# c64-uni-cart.net
KiCad netlist of a schematic drawn in EAGLE
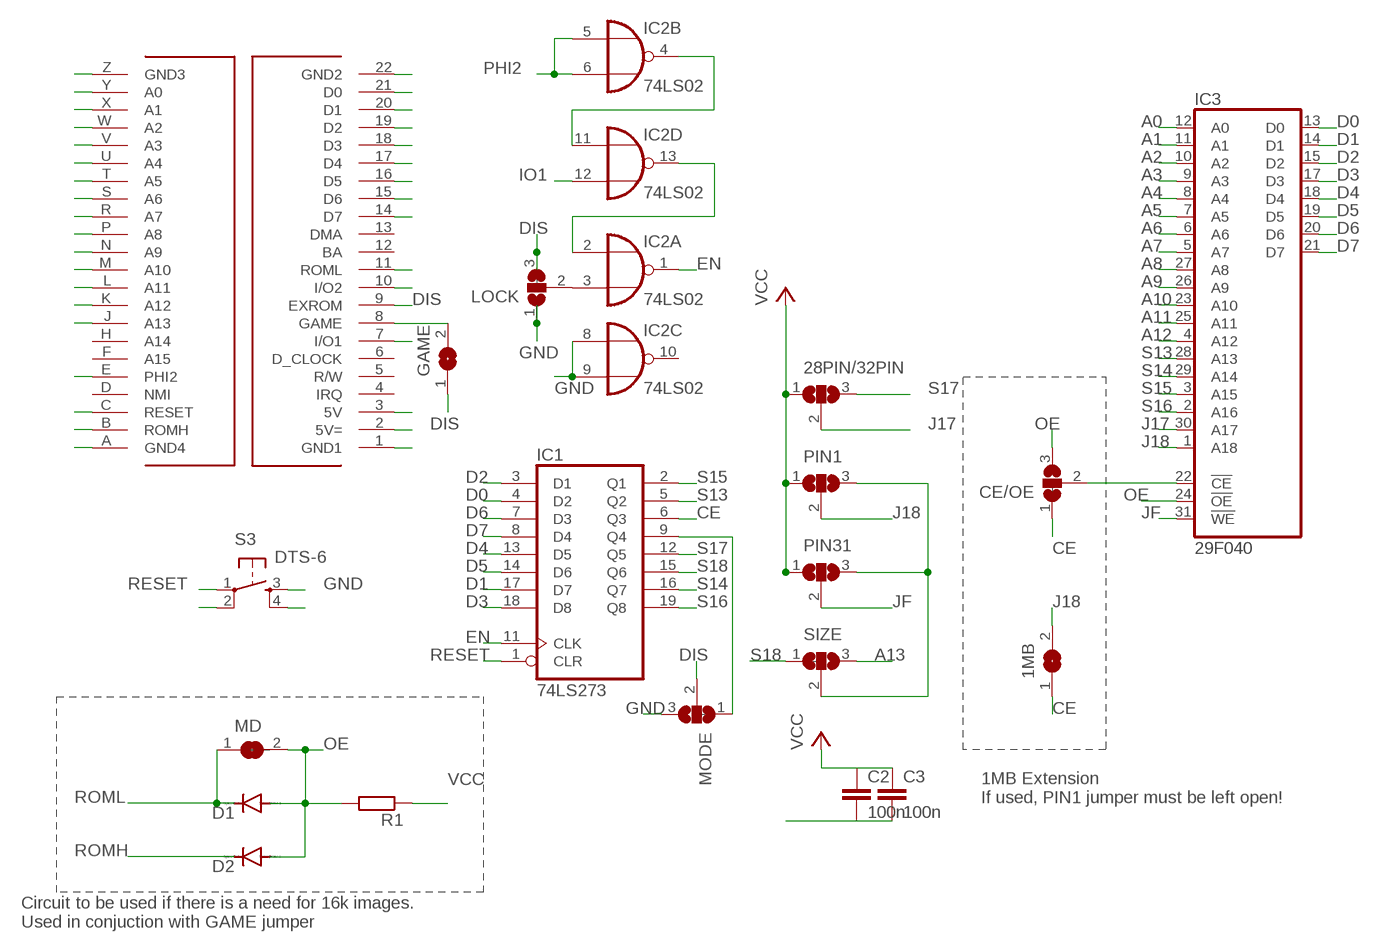
[diagram p0: schematic, sheet 1]

(export (version "E")
  (design (tool "Eeschema 10.0.6"))
  (components
    (comp (ref "1MB") (value "SJ") (footprint "eagle-import:SJ") (libsource (lib "eagle-import") (part "SJ")))
    (comp (ref "28PIN/32PIN")
      (value "SJ2W")
      (footprint "eagle-import:SJ_2")
      (libsource (lib "eagle-import") (part "SJ2W"))
    )
    (comp (ref "C2")
      (value "100n")
      (footprint "eagle-import:C025-024X044")
      (libsource (lib "eagle-import") (part "C-EU025-024X044"))
    )
    (comp (ref "C3")
      (value "100n")
      (footprint "eagle-import:C025-024X044")
      (libsource (lib "eagle-import") (part "C-EU025-024X044"))
    )
    (comp (ref "CE/OE")
      (value "SJ2W")
      (footprint "eagle-import:SJ_2")
      (libsource (lib "eagle-import") (part "SJ2W"))
    )
    (comp (ref "D1")
      (value "DIODE-MINIMELF")
      (footprint "eagle-import:MINIMELF")
      (libsource (lib "eagle-import") (part "DIODE-MINIMELF"))
    )
    (comp (ref "D2")
      (value "DIODE-MINIMELF")
      (footprint "eagle-import:MINIMELF")
      (libsource (lib "eagle-import") (part "DIODE-MINIMELF"))
    )
    (comp (ref "GAME")
      (value "SJ")
      (footprint "eagle-import:SJ")
      (libsource (lib "eagle-import") (part "SJ"))
    )
    (comp (ref "IC1")
      (value "74LS273")
      (footprint "eagle-import:DIL20")
      (libsource (lib "eagle-import") (part "74273NHCT"))
    )
    (comp (ref "IC2")
      (value "74LS02")
      (footprint "eagle-import:DIL14")
      (libsource (lib "eagle-import") (part "7402NLS"))
    )
    (comp (ref "IC3")
      (value "29F040")
      (footprint "eagle-import:DIL32-6")
      (libsource (lib "eagle-import") (part "AM29F040N"))
    )
    (comp (ref "LOCK")
      (value "SJ2W")
      (footprint "eagle-import:SJ_2")
      (libsource (lib "eagle-import") (part "SJ2W"))
    )
    (comp (ref "MD") (value "SJ") (footprint "eagle-import:SJ") (libsource (lib "eagle-import") (part "SJ")))
    (comp (ref "MODE")
      (value "SJ2W")
      (footprint "eagle-import:SJ_2")
      (libsource (lib "eagle-import") (part "SJ2W"))
    )
    (comp (ref "PIN1")
      (value "SJ2W")
      (footprint "eagle-import:SJ_2")
      (libsource (lib "eagle-import") (part "SJ2W"))
    )
    (comp (ref "PIN31")
      (value "SJ2W")
      (footprint "eagle-import:SJ_2")
      (libsource (lib "eagle-import") (part "SJ2W"))
    )
    (comp (ref "R1")
      (value "R-EU_R1206")
      (footprint "eagle-import:R1206")
      (libsource (lib "eagle-import") (part "R-EU_R1206"))
    )
    (comp (ref "S3")
      (value "DTS-6")
      (footprint "eagle-import:DTS-6")
      (libsource (lib "eagle-import") (part "DTS-6"))
    )
    (comp (ref "SIZE")
      (value "SJ2W")
      (footprint "eagle-import:SJ_2")
      (libsource (lib "eagle-import") (part "SJ2W"))
    )
    (comp (ref "U$1")
      (value "C64_CARTRIDGESTUMPY")
      (footprint "eagle-import:C64_STUMPY")
      (libsource (lib "eagle-import") (part "C64_CARTRIDGESTUMPY"))
    )
  )
  (nets
    (net (code "1") (name "/A0") (class "Default")
      (node (ref "IC3") (pin "12") (pinfunction "A0_12") (pintype "input"))
      (node (ref "U$1") (pin "Y") (pinfunction "A0_Y") (pintype "bidirectional"))
    )
    (net (code "2") (name "/A1") (class "Default")
      (node (ref "IC3") (pin "11") (pinfunction "A1_11") (pintype "input"))
      (node (ref "U$1") (pin "X") (pinfunction "A1_X") (pintype "bidirectional"))
    )
    (net (code "3") (name "/A2") (class "Default")
      (node (ref "IC3") (pin "10") (pinfunction "A2_10") (pintype "input"))
      (node (ref "U$1") (pin "W") (pinfunction "A2_W") (pintype "bidirectional"))
    )
    (net (code "4") (name "/A3") (class "Default")
      (node (ref "IC3") (pin "9") (pinfunction "A3_9") (pintype "input"))
      (node (ref "U$1") (pin "V") (pinfunction "A3_V") (pintype "bidirectional"))
    )
    (net (code "5") (name "/A4") (class "Default")
      (node (ref "IC3") (pin "8") (pinfunction "A4_8") (pintype "input"))
      (node (ref "U$1") (pin "U") (pinfunction "A4_U") (pintype "bidirectional"))
    )
    (net (code "6") (name "/A5") (class "Default")
      (node (ref "IC3") (pin "7") (pinfunction "A5_7") (pintype "input"))
      (node (ref "U$1") (pin "T") (pinfunction "A5_T") (pintype "bidirectional"))
    )
    (net (code "7") (name "/A6") (class "Default")
      (node (ref "IC3") (pin "6") (pinfunction "A6_6") (pintype "input"))
      (node (ref "U$1") (pin "S") (pinfunction "A6_S") (pintype "bidirectional"))
    )
    (net (code "8") (name "/A7") (class "Default")
      (node (ref "IC3") (pin "5") (pinfunction "A7_5") (pintype "input"))
      (node (ref "U$1") (pin "R") (pinfunction "A7_R") (pintype "bidirectional"))
    )
    (net (code "9") (name "/A8") (class "Default")
      (node (ref "IC3") (pin "27") (pinfunction "A8_27") (pintype "input"))
      (node (ref "U$1") (pin "P") (pinfunction "A8_P") (pintype "bidirectional"))
    )
    (net (code "10") (name "/A9") (class "Default")
      (node (ref "IC3") (pin "26") (pinfunction "A9_26") (pintype "input"))
      (node (ref "U$1") (pin "N") (pinfunction "A9_N") (pintype "bidirectional"))
    )
    (net (code "11") (name "/A10") (class "Default")
      (node (ref "IC3") (pin "23") (pinfunction "A10_23") (pintype "input"))
      (node (ref "U$1") (pin "M") (pinfunction "A10_M") (pintype "bidirectional"))
    )
    (net (code "12") (name "/A11") (class "Default")
      (node (ref "IC3") (pin "25") (pinfunction "A11_25") (pintype "input"))
      (node (ref "U$1") (pin "L") (pinfunction "A11_L") (pintype "bidirectional"))
    )
    (net (code "13") (name "/A12") (class "Default")
      (node (ref "IC3") (pin "4") (pinfunction "A12_4") (pintype "input"))
      (node (ref "U$1") (pin "K") (pinfunction "A12_K") (pintype "bidirectional"))
    )
    (net (code "14") (name "/A13") (class "Default")
      (node (ref "SIZE") (pin "3") (pinfunction "3_3") (pintype "passive"))
      (node (ref "U$1") (pin "J") (pinfunction "A13_J") (pintype "bidirectional"))
    )
    (net (code "15") (name "/CE") (class "Default")
      (node (ref "1MB") (pin "1") (pinfunction "1_1") (pintype "passive"))
      (node (ref "CE/OE") (pin "1") (pinfunction "1_1") (pintype "passive"))
      (node (ref "IC1") (pin "6") (pinfunction "Q3_6") (pintype "output"))
    )
    (net (code "16") (name "/D0") (class "Default")
      (node (ref "IC1") (pin "4") (pinfunction "D2_4") (pintype "input"))
      (node (ref "IC3") (pin "13") (pinfunction "D0_13") (pintype "tri_state"))
      (node (ref "U$1") (pin "21") (pinfunction "D0_21") (pintype "bidirectional"))
    )
    (net (code "17") (name "/D1") (class "Default")
      (node (ref "IC1") (pin "17") (pinfunction "D7_17") (pintype "input"))
      (node (ref "IC3") (pin "14") (pinfunction "D1_14") (pintype "tri_state"))
      (node (ref "U$1") (pin "20") (pinfunction "D1_20") (pintype "bidirectional"))
    )
    (net (code "18") (name "/D2") (class "Default")
      (node (ref "IC1") (pin "3") (pinfunction "D1_3") (pintype "input"))
      (node (ref "IC3") (pin "15") (pinfunction "D2_15") (pintype "tri_state"))
      (node (ref "U$1") (pin "19") (pinfunction "D2_19") (pintype "bidirectional"))
    )
    (net (code "19") (name "/D3") (class "Default")
      (node (ref "IC1") (pin "18") (pinfunction "D8_18") (pintype "input"))
      (node (ref "IC3") (pin "17") (pinfunction "D3_17") (pintype "tri_state"))
      (node (ref "U$1") (pin "18") (pinfunction "D3_18") (pintype "bidirectional"))
    )
    (net (code "20") (name "/D4") (class "Default")
      (node (ref "IC1") (pin "13") (pinfunction "D5_13") (pintype "input"))
      (node (ref "IC3") (pin "18") (pinfunction "D4_18") (pintype "tri_state"))
      (node (ref "U$1") (pin "17") (pinfunction "D4_17") (pintype "bidirectional"))
    )
    (net (code "21") (name "/D5") (class "Default")
      (node (ref "IC1") (pin "14") (pinfunction "D6_14") (pintype "input"))
      (node (ref "IC3") (pin "19") (pinfunction "D5_19") (pintype "tri_state"))
      (node (ref "U$1") (pin "16") (pinfunction "D5_16") (pintype "bidirectional"))
    )
    (net (code "22") (name "/D6") (class "Default")
      (node (ref "IC1") (pin "7") (pinfunction "D3_7") (pintype "input"))
      (node (ref "IC3") (pin "20") (pinfunction "D6_20") (pintype "tri_state"))
      (node (ref "U$1") (pin "15") (pinfunction "D6_15") (pintype "bidirectional"))
    )
    (net (code "23") (name "/D7") (class "Default")
      (node (ref "IC1") (pin "8") (pinfunction "D4_8") (pintype "input"))
      (node (ref "IC3") (pin "21") (pinfunction "D7_21") (pintype "tri_state"))
      (node (ref "U$1") (pin "14") (pinfunction "D7_14") (pintype "bidirectional"))
    )
    (net (code "24") (name "/DIS") (class "Default")
      (node (ref "GAME") (pin "1") (pinfunction "1_1") (pintype "passive"))
      (node (ref "LOCK") (pin "3") (pinfunction "3_3") (pintype "passive"))
      (node (ref "MODE") (pin "2") (pinfunction "2_2") (pintype "passive"))
      (node (ref "U$1") (pin "9") (pinfunction "EXROM_9") (pintype "bidirectional"))
    )
    (net (code "25") (name "/EN") (class "Default")
      (node (ref "IC1") (pin "11") (pinfunction "CLK_11") (pintype "input"))
      (node (ref "IC2") (pin "1") (pinfunction "O_1") (pintype "output"))
    )
    (net (code "26") (name "/GND") (class "Default")
      (node (ref "C2") (pin "2") (pinfunction "2_2") (pintype "passive"))
      (node (ref "C3") (pin "2") (pinfunction "2_2") (pintype "passive"))
      (node (ref "IC2") (pin "8") (pinfunction "I0_8") (pintype "input"))
      (node (ref "IC2") (pin "9") (pinfunction "I1_9") (pintype "input"))
      (node (ref "LOCK") (pin "1") (pinfunction "1_1") (pintype "passive"))
      (node (ref "MODE") (pin "3") (pinfunction "3_3") (pintype "passive"))
      (node (ref "S3") (pin "3") (pinfunction "3_3") (pintype "passive"))
      (node (ref "S3") (pin "4") (pinfunction "4_4") (pintype "passive"))
      (node (ref "U$1") (pin "1") (pinfunction "GND1_1") (pintype "bidirectional"))
      (node (ref "U$1") (pin "22") (pinfunction "GND2_22") (pintype "bidirectional"))
      (node (ref "U$1") (pin "A") (pinfunction "GND4_A") (pintype "bidirectional"))
      (node (ref "U$1") (pin "Z") (pinfunction "GND3_Z") (pintype "bidirectional"))
    )
    (net (code "27") (name "/IO1") (class "Default")
      (node (ref "IC2") (pin "12") (pinfunction "I1_12") (pintype "input"))
      (node (ref "U$1") (pin "7") (pinfunction "I/O1_7") (pintype "bidirectional"))
    )
    (net (code "28") (name "/J17") (class "Default")
      (node (ref "28PIN/32PIN") (pin "2") (pinfunction "2_2") (pintype "passive"))
      (node (ref "IC3") (pin "30") (pinfunction "A17_30") (pintype "input"))
    )
    (net (code "29") (name "/J18") (class "Default")
      (node (ref "1MB") (pin "2") (pinfunction "2_2") (pintype "passive"))
      (node (ref "IC3") (pin "1") (pinfunction "A18_1") (pintype "input"))
      (node (ref "PIN1") (pin "2") (pinfunction "2_2") (pintype "passive"))
    )
    (net (code "30") (name "/JF") (class "Default")
      (node (ref "IC3") (pin "31") (pinfunction "~{WE}_31") (pintype "input"))
      (node (ref "PIN31") (pin "2") (pinfunction "2_2") (pintype "passive"))
    )
    (net (code "31") (name "/OE") (class "Default")
      (node (ref "CE/OE") (pin "3") (pinfunction "3_3") (pintype "passive"))
      (node (ref "D1") (pin "A") (pinfunction "A_A") (pintype "passive"))
      (node (ref "D2") (pin "A") (pinfunction "A_A") (pintype "passive"))
      (node (ref "IC3") (pin "24") (pinfunction "~{OE}_24") (pintype "input"))
      (node (ref "MD") (pin "2") (pinfunction "2_2") (pintype "passive"))
      (node (ref "R1") (pin "2") (pinfunction "2_2") (pintype "passive"))
    )
    (net (code "32") (name "/PHI2") (class "Default")
      (node (ref "IC2") (pin "5") (pinfunction "I0_5") (pintype "input"))
      (node (ref "IC2") (pin "6") (pinfunction "I1_6") (pintype "input"))
      (node (ref "U$1") (pin "E") (pinfunction "PHI2_E") (pintype "bidirectional"))
    )
    (net (code "33") (name "/RESET") (class "Default")
      (node (ref "IC1") (pin "1") (pinfunction "CLR_1") (pintype "input"))
      (node (ref "S3") (pin "1") (pinfunction "1_1") (pintype "passive"))
      (node (ref "S3") (pin "2") (pinfunction "2_2") (pintype "passive"))
      (node (ref "U$1") (pin "C") (pinfunction "RESET_C") (pintype "bidirectional"))
    )
    (net (code "34") (name "/ROMH") (class "Default")
      (node (ref "D2") (pin "C") (pinfunction "C_C") (pintype "passive"))
      (node (ref "U$1") (pin "B") (pinfunction "ROMH_B") (pintype "bidirectional"))
    )
    (net (code "35") (name "/ROML") (class "Default")
      (node (ref "D1") (pin "C") (pinfunction "C_C") (pintype "passive"))
      (node (ref "MD") (pin "1") (pinfunction "1_1") (pintype "passive"))
      (node (ref "U$1") (pin "11") (pinfunction "ROML_11") (pintype "bidirectional"))
    )
    (net (code "36") (name "/S13") (class "Default")
      (node (ref "IC1") (pin "5") (pinfunction "Q2_5") (pintype "output"))
      (node (ref "IC3") (pin "28") (pinfunction "A13_28") (pintype "input"))
    )
    (net (code "37") (name "/S14") (class "Default")
      (node (ref "IC1") (pin "16") (pinfunction "Q7_16") (pintype "output"))
      (node (ref "IC3") (pin "29") (pinfunction "A14_29") (pintype "input"))
    )
    (net (code "38") (name "/S15") (class "Default")
      (node (ref "IC1") (pin "2") (pinfunction "Q1_2") (pintype "output"))
      (node (ref "IC3") (pin "3") (pinfunction "A15_3") (pintype "input"))
    )
    (net (code "39") (name "/S16") (class "Default")
      (node (ref "IC1") (pin "19") (pinfunction "Q8_19") (pintype "output"))
      (node (ref "IC3") (pin "2") (pinfunction "A16_2") (pintype "input"))
    )
    (net (code "40") (name "/S17") (class "Default")
      (node (ref "28PIN/32PIN") (pin "3") (pinfunction "3_3") (pintype "passive"))
      (node (ref "IC1") (pin "12") (pinfunction "Q5_12") (pintype "output"))
    )
    (net (code "41") (name "/S18") (class "Default")
      (node (ref "IC1") (pin "15") (pinfunction "Q6_15") (pintype "output"))
      (node (ref "SIZE") (pin "1") (pinfunction "1_1") (pintype "passive"))
    )
    (net (code "42") (name "Net-(IC1A-Q4)") (class "Default")
      (node (ref "IC1") (pin "9") (pinfunction "Q4_9") (pintype "output"))
      (node (ref "MODE") (pin "1") (pinfunction "1_1") (pintype "passive"))
    )
    (net (code "43") (name "Net-(IC2A-I0)") (class "Default")
      (node (ref "IC2") (pin "13") (pinfunction "O_13") (pintype "output"))
      (node (ref "IC2") (pin "2") (pinfunction "I0_2") (pintype "input"))
    )
    (net (code "44") (name "Net-(IC2A-I1)") (class "Default")
      (node (ref "IC2") (pin "3") (pinfunction "I1_3") (pintype "input"))
      (node (ref "LOCK") (pin "2") (pinfunction "2_2") (pintype "passive"))
    )
    (net (code "45") (name "Net-(IC2B-O)") (class "Default")
      (node (ref "IC2") (pin "11") (pinfunction "I0_11") (pintype "input"))
      (node (ref "IC2") (pin "4") (pinfunction "O_4") (pintype "output"))
    )
    (net (code "46") (name "Net-(IC3A-~{CE})") (class "Default")
      (node (ref "CE/OE") (pin "2") (pinfunction "2_2") (pintype "passive"))
      (node (ref "IC3") (pin "22") (pinfunction "~{CE}_22") (pintype "input"))
    )
    (net (code "47") (name "Net-(PIN1-Pad3)") (class "Default")
      (node (ref "PIN1") (pin "3") (pinfunction "3_3") (pintype "passive"))
      (node (ref "PIN31") (pin "3") (pinfunction "3_3") (pintype "passive"))
      (node (ref "SIZE") (pin "2") (pinfunction "2_2") (pintype "passive"))
    )
    (net (code "48") (name "Net-(U$1-GAME)") (class "Default")
      (node (ref "GAME") (pin "2") (pinfunction "2_2") (pintype "passive"))
      (node (ref "U$1") (pin "8") (pinfunction "GAME_8") (pintype "bidirectional"))
    )
    (net (code "49") (name "VCC") (class "Default")
      (node (ref "28PIN/32PIN") (pin "1") (pinfunction "1_1") (pintype "passive"))
      (node (ref "C2") (pin "1") (pinfunction "1_1") (pintype "passive"))
      (node (ref "C3") (pin "1") (pinfunction "1_1") (pintype "passive"))
      (node (ref "PIN1") (pin "1") (pinfunction "1_1") (pintype "passive"))
      (node (ref "PIN31") (pin "1") (pinfunction "1_1") (pintype "passive"))
      (node (ref "R1") (pin "1") (pinfunction "1_1") (pintype "passive"))
      (node (ref "U$1") (pin "2") (pinfunction "5V=_2") (pintype "bidirectional"))
      (node (ref "U$1") (pin "3") (pinfunction "5V_3") (pintype "bidirectional"))
    )
    (net (code "50") (name "unconnected-(IC2C-O-Pad10)") (class "Default")
      (node (ref "IC2") (pin "10") (pinfunction "O_10") (pintype "output"))
    )
    (net (code "51") (name "unconnected-(U$1-A14-PadH)") (class "Default")
      (node (ref "U$1") (pin "H") (pinfunction "A14_H") (pintype "bidirectional"))
    )
    (net (code "52") (name "unconnected-(U$1-A15-PadF)") (class "Default")
      (node (ref "U$1") (pin "F") (pinfunction "A15_F") (pintype "bidirectional"))
    )
    (net (code "53") (name "unconnected-(U$1-BA-Pad12)") (class "Default")
      (node (ref "U$1") (pin "12") (pinfunction "BA_12") (pintype "bidirectional"))
    )
    (net (code "54") (name "unconnected-(U$1-DMA-Pad13)") (class "Default")
      (node (ref "U$1") (pin "13") (pinfunction "DMA_13") (pintype "bidirectional"))
    )
    (net (code "55") (name "unconnected-(U$1-D_CLOCK-Pad6)") (class "Default")
      (node (ref "U$1") (pin "6") (pinfunction "D_CLOCK_6") (pintype "bidirectional"))
    )
    (net (code "56") (name "unconnected-(U$1-IRQ-Pad4)") (class "Default")
      (node (ref "U$1") (pin "4") (pinfunction "IRQ_4") (pintype "bidirectional"))
    )
    (net (code "57") (name "unconnected-(U$1-I{slash}O2-Pad10)") (class "Default")
      (node (ref "U$1") (pin "10") (pinfunction "I/O2_10") (pintype "bidirectional"))
    )
    (net (code "58") (name "unconnected-(U$1-NMI-PadD)") (class "Default")
      (node (ref "U$1") (pin "D") (pinfunction "NMI_D") (pintype "bidirectional"))
    )
    (net (code "59") (name "unconnected-(U$1-R{slash}W-Pad5)") (class "Default")
      (node (ref "U$1") (pin "5") (pinfunction "R/W_5") (pintype "bidirectional"))
    )
  )
)
